# power_management.net
KiCad netlist of a schematic drawn in Altium Designer
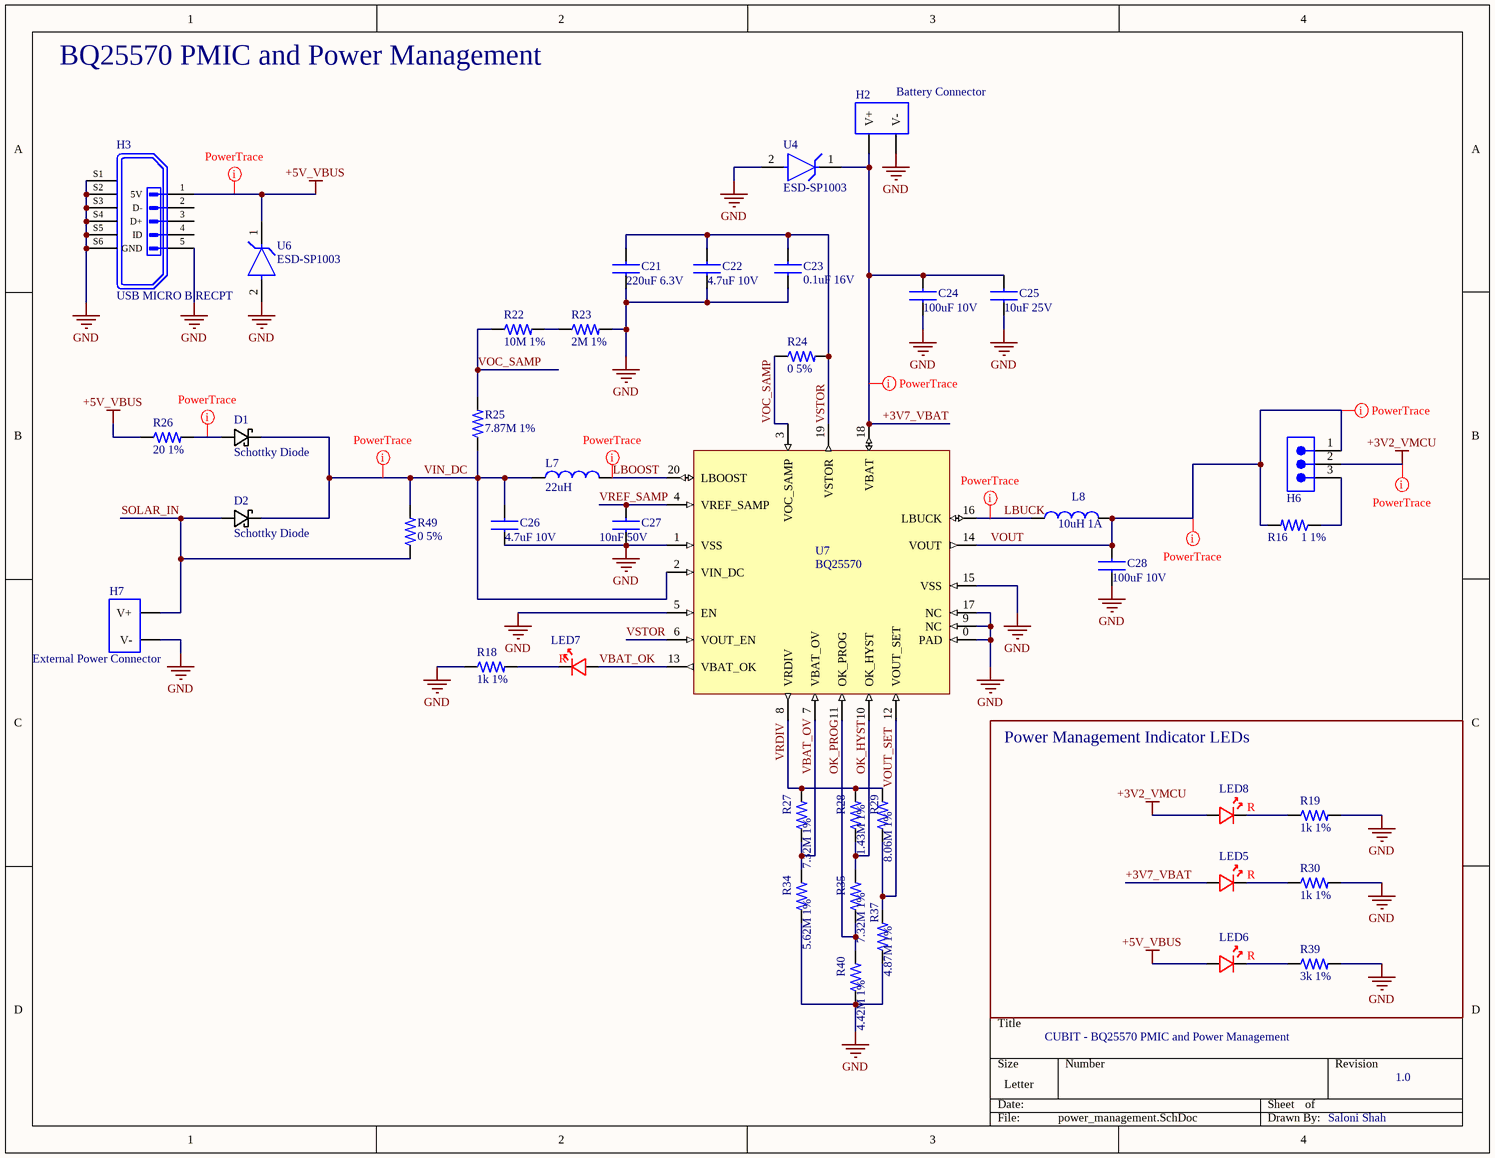
[diagram p0: power_management.SchDoc]

(export (version "E")
  (design (tool "Eeschema 10.0.6"))
  (components
    (comp (ref "C21")
      (value "220uF 6.3V")
      (footprint "Chip_1210_3.2x2.5")
      (description "Cap 220uF 6.3volts X5R 20%")
      (fields
        (field (name "MANUFACTURER") "Murata")
        (field (name "MANUFACTURER PART NUMBER") "GRM32ER60J227ME05L")
      )
      (libsource (lib "LPEDT_proj_lib") (part "GRM32ER60J227ME05L"))
    )
    (comp (ref "C22")
      (value "4.7uF 10V")
      (footprint "LPEDT_proj_lib:CAP_0603_1MM")
      (description "Cap CL10 Series 4.7 uF 10 V ±10 % Tolerance X5R SMT Multilayer Ceramic Capacitor")
      (fields
        (field (name "MANUFACTURER") "Samsung")
        (field (name "MANUFACTURER PART NUMBER") "CL10A475KP8NNNC")
      )
      (libsource (lib "LPEDT_proj_lib") (part "CL10A475KP8NNNC"))
    )
    (comp (ref "C23")
      (value "0.1uF 16V")
      (footprint "LPEDT_proj_lib:CAP_0603_1MM")
      (description "Cap Ceramic 0.1uF 16V X7R 10% SMD 0805 125°C Paper T/R")
      (fields
        (field (name "MANUFACTURER") "KEMET")
        (field (name "MANUFACTURER PART NUMBER") "C0805C104K4RACAUTO")
      )
      (libsource (lib "LPEDT_proj_lib") (part "C0805C104K4RACAUTO"))
    )
    (comp (ref "C24")
      (value "100uF 10V")
      (footprint "Chip_1210_3.2x2.5")
      (description "Cap 100uF ±20% 10V X5R 1210")
      (fields
        (field (name "MANUFACTURER") "Samsung")
        (field (name "MANUFACTURER PART NUMBER") "CL32A107MPVNNNE")
      )
      (libsource (lib "LPEDT_proj_lib") (part "CL32A107MPVNNNE"))
    )
    (comp (ref "C25")
      (value "10uF 25V")
      (footprint "LPEDT_proj_lib:CAP_0805_02X125")
      (description "Cap 0805 25 V 10 uF ±20% Tolerance X5R Monolithic Ceramic Chip Capacitor")
      (fields
        (field (name "MANUFACTURER") "Murata")
        (field (name "MANUFACTURER PART NUMBER") "GRM21BR61E106KA73K")
      )
      (libsource (lib "LPEDT_proj_lib") (part "GRM21BR61E106KA73K"))
    )
    (comp (ref "C26")
      (value "4.7uF 10V")
      (footprint "LPEDT_proj_lib:CAP_0603_1MM")
      (description "Cap CL10 Series 4.7 uF 10 V ±10 % Tolerance X5R SMT Multilayer Ceramic Capacitor")
      (fields
        (field (name "MANUFACTURER") "Samsung")
        (field (name "MANUFACTURER PART NUMBER") "CL10A475KP8NNNC")
      )
      (libsource (lib "LPEDT_proj_lib") (part "CL10A475KP8NNNC"))
    )
    (comp (ref "C27")
      (value "10nF 50V")
      (footprint "LPEDT_proj_lib:CAP_0805_02X125")
      (description "Cap 10nF ±10% 50V X7R 0805")
      (fields
        (field (name "MANUFACTURER") "Samsung")
        (field (name "MANUFACTURER PART NUMBER") "CL21B103KBCNNNC")
      )
      (libsource (lib "LPEDT_proj_lib") (part "CL21B103KBCNNNC"))
    )
    (comp (ref "C28")
      (value "100uF 10V")
      (footprint "Chip_1210_3.2x2.5")
      (description "Cap 100uF ±20% 10V X5R 1210")
      (fields
        (field (name "MANUFACTURER") "Samsung")
        (field (name "MANUFACTURER PART NUMBER") "CL32A107MPVNNNE")
      )
      (libsource (lib "LPEDT_proj_lib") (part "CL32A107MPVNNNE"))
    )
    (comp (ref "D1")
      (value "Schottky Diode")
      (footprint "SCHOTTKY4336X33N")
      (description "LSM115J Series 15 V 1 A Surface Mount Schottky Rectifier - DO-214BA")
      (fields
        (field (name "MANUFACTURER") "Microchip")
        (field (name "MANUFACTURER PART NUMBER") "LSM115JE3/TR13")
      )
      (libsource (lib "LPEDT_proj_lib") (part "LSM115JE3/TR13"))
    )
    (comp (ref "D2")
      (value "Schottky Diode")
      (footprint "SCHOTTKY4336X33N")
      (description "LSM115J Series 15 V 1 A Surface Mount Schottky Rectifier - DO-214BA")
      (fields
        (field (name "MANUFACTURER") "Microchip")
        (field (name "MANUFACTURER PART NUMBER") "LSM115JE3/TR13")
      )
      (libsource (lib "LPEDT_proj_lib") (part "LSM115JE3/TR13"))
    )
    (comp (ref "H2")
      (value "Battery Connector")
      (footprint "BAT_CONN")
      (description "2.00mm Pitch Mi ll System Wire-to-Board Header, Surface Mount, Single Row, Vertical, 2 Circuits")
      (fields (field (name "MANUFACTURER") "Molex") (field (name "MANUFACTURER PART NUMBER") "0554600272"))
      (libsource (lib "LPEDT_proj_lib") (part "0554600272"))
    )
    (comp (ref "H3")
      (value "USB MICRO B RECPT")
      (footprint "MICROUSB_AMPHENOL_10118194-0001LF")
      (description "USB - micro B USB 2.0 Receptacle Connector 5 Position Surface Mount, Right Angle; Through Hole")
      (fields
        (field (name "MANUFACTURER") "Amphenol FCI")
        (field (name "MANUFACTURER PART NUMBER") "10118194-0001LF")
      )
      (libsource (lib "LPEDT_proj_lib") (part "10118194-0001LF"))
    )
    (comp (ref "H6")
      (value "PREC003SAAN-RC")
      (footprint "LPEDT_proj_lib:3_PIN_100mil")
      (description "Connector Header Through Hole 3 position 0.100\" (2.54mm)")
      (fields (field (name "DIGIKEY PART") "S1012EC-03-ND") (field (name "LCSC PART#") "C429954"))
      (libsource (lib "LPEDT_proj_lib") (part "SW_3Pin_100mil_Switch"))
    )
    (comp (ref "H7")
      (value "External Power Connector")
      (footprint "LPEDT_proj_lib:2_PIN_100mil")
      (libsource (lib "LPEDT_proj_lib") (part "ext_pwr_conn"))
    )
    (comp (ref "L7")
      (value "22uH")
      (footprint "2_IND_3x3")
      (description "Inductor Power Shielded Wirewound 22uH 20% 1MHz Ferrite 0.87A 0.496Ohm DCR 1212 T/R")
      (fields
        (field (name "MANUFACTURER") "TDK")
        (field (name "MANUFACTURER PART NUMBER") "VLS3015CX-220M-1")
      )
      (libsource (lib "LPEDT_proj_lib") (part "VLS3015CX-220M-1"))
    )
    (comp (ref "L8")
      (value "10uH 1A")
      (footprint "2_chip_2.5x2")
      (description "Inductor Power Shielded Multi-Layer 10uH 20% 1MHz Metal 0.85A 0.46Ohm DCR 1008 T/R")
      (fields
        (field (name "MANUFACTURER") "Murata")
        (field (name "MANUFACTURER PART NUMBER") "1239AS-H-100M=P2")
      )
      (libsource (lib "LPEDT_proj_lib") (part "1239AS-H-100M=P2"))
    )
    (comp (ref "LED5")
      (value "150060RS75000")
      (footprint "LED_0603_RED_WL-SMCW")
      (description "LED Low-Power Uni-Color Red 630nm 2V 2-Pin Chip 0603(1608Metric) T/R")
      (fields (field (name "MANUFACTURER") "Wurth Electronics"))
      (libsource (lib "LPEDT_proj_lib") (part "150060RS75000"))
    )
    (comp (ref "LED6")
      (value "150060RS75000")
      (footprint "LED_0603_RED_WL-SMCW")
      (description "LED Low-Power Uni-Color Red 630nm 2V 2-Pin Chip 0603(1608Metric) T/R")
      (fields (field (name "MANUFACTURER") "Wurth Electronics"))
      (libsource (lib "LPEDT_proj_lib") (part "150060RS75000"))
    )
    (comp (ref "LED7")
      (value "150060RS75000")
      (footprint "LED_0603_RED_WL-SMCW")
      (description "LED Low-Power Uni-Color Red 630nm 2V 2-Pin Chip 0603(1608Metric) T/R")
      (fields (field (name "MANUFACTURER") "Wurth Electronics"))
      (libsource (lib "LPEDT_proj_lib") (part "150060RS75000"))
    )
    (comp (ref "LED8")
      (value "150060RS75000")
      (footprint "LED_0603_RED_WL-SMCW")
      (description "LED Low-Power Uni-Color Red 630nm 2V 2-Pin Chip 0603(1608Metric) T/R")
      (fields (field (name "MANUFACTURER") "Wurth Electronics"))
      (libsource (lib "LPEDT_proj_lib") (part "150060RS75000"))
    )
    (comp (ref "R16")
      (value "1 1%")
      (footprint "LPEDT_proj_lib:CAP_0603_1MM")
      (description "Res 1 Ohm 1% 1/10W ±200ppm/°C Molded SMD SMD Paper T/R")
      (fields
        (field (name "MANUFACTURER") "Yageo")
        (field (name "MANUFACTURER PART NUMBER") "RC0603FR-101RL")
      )
      (libsource (lib "LPEDT_proj_lib") (part "RC0603FR-101RL"))
    )
    (comp (ref "R18")
      (value "1k 1%")
      (footprint "2_Chip_0603_RMCF")
      (description "Res 1K Ohm 1% 0.1W(1/10W) ±100ppm/C Pad SMD Automotive T/R")
      (fields
        (field (name "MANUFACTURER") "Stackpole Electronics")
        (field (name "MANUFACTURER PART NUMBER") "RMCF0603FT1K00")
      )
      (libsource (lib "LPEDT_proj_lib") (part "RMCF0603FT1K00"))
    )
    (comp (ref "R19")
      (value "1k 1%")
      (footprint "2_Chip_0603_RMCF")
      (description "Res 1K Ohm 1% 0.1W(1/10W) ±100ppm/C Pad SMD Automotive T/R")
      (fields
        (field (name "MANUFACTURER") "Stackpole Electronics")
        (field (name "MANUFACTURER PART NUMBER") "RMCF0603FT1K00")
      )
      (libsource (lib "LPEDT_proj_lib") (part "RMCF0603FT1K00"))
    )
    (comp (ref "R22")
      (value "10M 1%")
      (footprint "2_Chip_0603_RMCF")
      (description "Res 10M Ohm 1% 1/10W ±200ppm/°C Molded SMD SMD Paper T/R")
      (fields
        (field (name "MANUFACTURER") "Stackpole Electronics")
        (field (name "MANUFACTURER PART NUMBER") "RMCF0603FT10M0")
      )
      (libsource (lib "LPEDT_proj_lib") (part "RMCF0603FT10M0"))
    )
    (comp (ref "R23")
      (value "2M 1%")
      (footprint "2_Chip_0603_RMCF")
      (description "RES 2M OHM 1% 1/10W 0603")
      (fields
        (field (name "MANUFACTURER") "Stackpole Electronics")
        (field (name "MANUFACTURER PART NUMBER") "RMCF0603FT2M00")
      )
      (libsource (lib "LPEDT_proj_lib") (part "RMCF0603FT2M00"))
    )
    (comp (ref "R24")
      (value "0 5%")
      (footprint "CAP_0402_1mm")
      (description "Res 0 Ohms ±5% 0.063 W 0402 Thick Film Surface Mount Chip Resistor")
      (fields
        (field (name "MANUFACTURER") "Samsung")
        (field (name "MANUFACTURER PART NUMBER") "RC1005J000CS")
      )
      (libsource (lib "LPEDT_proj_lib") (part "RC1005J000CS"))
    )
    (comp (ref "R25")
      (value "7.87M 1%")
      (footprint "2_Chip_0603_RMCF")
      (description "Res 7.87M Ohm 1% 1/10W ±200ppm/°C Molded SMD SMD Paper T/R")
      (fields
        (field (name "MANUFACTURER") "Stackpole Electronics")
        (field (name "MANUFACTURER PART NUMBER") "RMCF0603FT7M87")
      )
      (libsource (lib "LPEDT_proj_lib") (part "RMCF0603FT7M87"))
    )
    (comp (ref "R26")
      (value "20 1%")
      (footprint "2_Chip_0603_RMCF")
      (description "Res High Voltage 0603 20 Ohm 1/10W 1% SMD")
      (fields (field (name "MANUFACTURER") "Rohm") (field (name "MANUFACTURER PART NUMBER") "KTR03EZPF20R0"))
      (libsource (lib "LPEDT_proj_lib") (part "KTR03EZPF20R0"))
    )
    (comp (ref "R27")
      (value "7.32M 1%")
      (footprint "2_Chip_0603_RMCF")
      (description "Res 7.32M Ohm 1% 1/10W ±200ppm/°C Molded SMD SMD Paper T/R")
      (fields
        (field (name "MANUFACTURER") "Stackpole Electronics")
        (field (name "MANUFACTURER PART NUMBER") "RMCF0603FT7M32")
      )
      (libsource (lib "LPEDT_proj_lib") (part "RMCF0603FT7M32"))
    )
    (comp (ref "R28")
      (value "1.43M 1%")
      (footprint "2_Chip_0603_RMCF")
      (description "Res 1.43M Ohm 1% 1/10W ±200ppm/°C Molded SMD SMD Paper T/R")
      (fields
        (field (name "MANUFACTURER") "Stackpole Electronics")
        (field (name "MANUFACTURER PART NUMBER") "RMCF0603FT1M43")
      )
      (libsource (lib "LPEDT_proj_lib") (part "RMCF0603FT1M43"))
    )
    (comp (ref "R29")
      (value "8.06M 1%")
      (footprint "2_Chip_0603_RMCF")
      (description "Res 8.06M Ohm 1% 1/10W ±200ppm/°C Molded SMD SMD Paper T/R")
      (fields
        (field (name "MANUFACTURER") "Stackpole Electronics")
        (field (name "MANUFACTURER PART NUMBER") "RMCF0603FT8M06")
      )
      (libsource (lib "LPEDT_proj_lib") (part "RMCF0603FT8M06"))
    )
    (comp (ref "R30")
      (value "1k 1%")
      (footprint "2_Chip_0603_RMCF")
      (description "Res 1K Ohm 1% 0.1W(1/10W) ±100ppm/C Pad SMD Automotive T/R")
      (fields
        (field (name "MANUFACTURER") "Stackpole Electronics")
        (field (name "MANUFACTURER PART NUMBER") "RMCF0603FT1K00")
      )
      (libsource (lib "LPEDT_proj_lib") (part "RMCF0603FT1K00"))
    )
    (comp (ref "R34")
      (value "5.62M 1%")
      (footprint "2_Chip_0603_RMCF")
      (description "Res 5.62M Ohm 1% 1/10W ±200ppm/°C Molded SMD SMD Paper T/R")
      (fields
        (field (name "MANUFACTURER") "Stackpole Electronics")
        (field (name "MANUFACTURER PART NUMBER") "RMCF0603FT5M62")
      )
      (libsource (lib "LPEDT_proj_lib") (part "RMCF0603FT5M62"))
    )
    (comp (ref "R35")
      (value "7.32M 1%")
      (footprint "2_Chip_0603_RMCF")
      (description "Res 7.32M Ohm 1% 1/10W ±200ppm/°C Molded SMD SMD Paper T/R")
      (fields
        (field (name "MANUFACTURER") "Stackpole Electronics")
        (field (name "MANUFACTURER PART NUMBER") "RMCF0603FT7M32")
      )
      (libsource (lib "LPEDT_proj_lib") (part "RMCF0603FT7M32"))
    )
    (comp (ref "R37")
      (value "4.87M 1%")
      (footprint "2_Chip_0603_RMCF")
      (description "Res 4.87M Ohm 1% 1/10W ±200ppm/°C Molded SMD SMD Paper T/R")
      (fields
        (field (name "MANUFACTURER") "Stackpole Electronics")
        (field (name "MANUFACTURER PART NUMBER") "RMCF0603FT4M87")
      )
      (libsource (lib "LPEDT_proj_lib") (part "RMCF0603FT4M87"))
    )
    (comp (ref "R39")
      (value "3k 1%")
      (footprint "LPEDT_proj_lib:CAP_0603_1MM")
      (description "Res 3000Ω ± 1.00% 0.1W ± 100ppm/℃ 0603")
      (fields
        (field (name "MANUFACTURER") "Yageo")
        (field (name "MANUFACTURER PART NUMBER") "RC0603FR-073KL")
      )
      (libsource (lib "LPEDT_proj_lib") (part "RC0603FR-073KL"))
    )
    (comp (ref "R40")
      (value "4.42M 1%")
      (footprint "2_Chip_0603_RMCF")
      (description "Res 4.42M Ohm 1% 1/10W ±200ppm/°C Molded SMD SMD Paper T/R")
      (fields
        (field (name "MANUFACTURER") "Stackpole Electronics")
        (field (name "MANUFACTURER PART NUMBER") "RMCF0603FT4M42")
      )
      (libsource (lib "LPEDT_proj_lib") (part "RMCF0603FT4M42"))
    )
    (comp (ref "R49")
      (value "0 5%")
      (footprint "CAP_0402_1mm")
      (description "Res 0 Ohms ±5% 0.063 W 0402 Thick Film Surface Mount Chip Resistor")
      (fields
        (field (name "MANUFACTURER") "Samsung")
        (field (name "MANUFACTURER PART NUMBER") "RC1005J000CS")
      )
      (libsource (lib "LPEDT_proj_lib") (part "RC1005J000CS"))
    )
    (comp (ref "U4")
      (value "ESD-SP1003")
      (footprint "Littelfuse_Inc_SP1003_MFG")
      (description "TVS DIODE 5VWM 12VC SOD723")
      (fields
        (field (name "MANUFACTURER") "Littelfuse")
        (field (name "MANUFACTURER PART NUMBER") "SP1003-01DTG")
      )
      (libsource (lib "LPEDT_proj_lib") (part "SP1003-01DTG"))
    )
    (comp (ref "U6")
      (value "ESD-SP1003")
      (footprint "Littelfuse_Inc_SP1003_MFG")
      (description "TVS DIODE 5VWM 12VC SOD723")
      (fields
        (field (name "MANUFACTURER") "Littelfuse")
        (field (name "MANUFACTURER PART NUMBER") "SP1003-01DTG")
      )
      (libsource (lib "LPEDT_proj_lib") (part "SP1003-01DTG"))
    )
    (comp (ref "U7")
      (value "BQ25570")
      (footprint "21_QFN_35x35")
      (description "Switching Battery Charger Li-Ion/Li-Pol/Supercapacitor 110mA 2.2V to 5.5V 20-Pin VQFN EP T/R")
      (fields
        (field (name "MANUFACTURER") "Texas Instruments")
        (field (name "MANUFACTURER PART NUMBER") "BQ25570RGRT")
      )
      (libsource (lib "LPEDT_proj_lib") (part "BQ25570RGRT"))
    )
  )
  (nets
    (net (code "1") (name "+3V2_VMCU") (class "Default")
      (node (ref "H6") (pin "2") (pinfunction "2_2") (pintype "passive"))
      (node (ref "LED8") (pin "A") (pinfunction "A_A") (pintype "passive"))
    )
    (net (code "2") (name "+5V_VBUS") (class "Default")
      (node (ref "H3") (pin "1") (pinfunction "5V_1") (pintype "power_in"))
      (node (ref "LED6") (pin "A") (pinfunction "A_A") (pintype "passive"))
      (node (ref "R26") (pin "1") (pinfunction "1_1") (pintype "passive"))
      (node (ref "U6") (pin "1") (pinfunction "C_1") (pintype "passive"))
    )
    (net (code "3") (name "/+3V7_VBAT") (class "Default")
      (node (ref "C24") (pin "1") (pinfunction "1_1") (pintype "passive"))
      (node (ref "C25") (pin "1") (pinfunction "1_1") (pintype "passive"))
      (node (ref "H2") (pin "V+") (pinfunction "V+_V+") (pintype "passive"))
      (node (ref "LED5") (pin "A") (pinfunction "A_A") (pintype "passive"))
      (node (ref "U4") (pin "1") (pinfunction "C_1") (pintype "passive"))
      (node (ref "U7") (pin "18") (pinfunction "VBAT_18") (pintype "bidirectional"))
    )
    (net (code "4") (name "/LBOOST") (class "Default")
      (node (ref "L7") (pin "2") (pinfunction "2_2") (pintype "passive"))
      (node (ref "U7") (pin "20") (pinfunction "LBOOST_20") (pintype "bidirectional"))
    )
    (net (code "5") (name "/LBUCK") (class "Default")
      (node (ref "L8") (pin "1") (pinfunction "1_1") (pintype "passive"))
      (node (ref "U7") (pin "16") (pinfunction "LBUCK_16") (pintype "bidirectional"))
    )
    (net (code "6") (name "/OK_HYST") (class "Default")
      (node (ref "R28") (pin "1") (pinfunction "1_1") (pintype "passive"))
      (node (ref "R35") (pin "2") (pinfunction "2_2") (pintype "passive"))
      (node (ref "U7") (pin "10") (pinfunction "OK_HYST_10") (pintype "input"))
    )
    (net (code "7") (name "/OK_PROG") (class "Default")
      (node (ref "R35") (pin "1") (pinfunction "1_1") (pintype "passive"))
      (node (ref "R40") (pin "2") (pinfunction "2_2") (pintype "passive"))
      (node (ref "U7") (pin "11") (pinfunction "OK_PROG_11") (pintype "input"))
    )
    (net (code "8") (name "/SOLAR_IN") (class "Default")
      (node (ref "D2") (pin "A") (pinfunction "A_A") (pintype "passive"))
      (node (ref "H7") (pin "1") (pinfunction "V+_1") (pintype "passive"))
      (node (ref "R49") (pin "1") (pinfunction "1_1") (pintype "passive"))
    )
    (net (code "9") (name "/VBAT_OK") (class "Default")
      (node (ref "LED7") (pin "A") (pinfunction "A_A") (pintype "passive"))
      (node (ref "U7") (pin "13") (pinfunction "VBAT_OK_13") (pintype "output"))
    )
    (net (code "10") (name "/VBAT_OV") (class "Default")
      (node (ref "R27") (pin "1") (pinfunction "1_1") (pintype "passive"))
      (node (ref "R34") (pin "2") (pinfunction "2_2") (pintype "passive"))
      (node (ref "U7") (pin "7") (pinfunction "VBAT_OV_7") (pintype "input"))
    )
    (net (code "11") (name "/VIN_DC") (class "Default")
      (node (ref "C26") (pin "1") (pinfunction "1_1") (pintype "passive"))
      (node (ref "D1") (pin "C") (pinfunction "C_C") (pintype "passive"))
      (node (ref "D2") (pin "C") (pinfunction "C_C") (pintype "passive"))
      (node (ref "L7") (pin "1") (pinfunction "1_1") (pintype "passive"))
      (node (ref "R25") (pin "1") (pinfunction "1_1") (pintype "passive"))
      (node (ref "R49") (pin "2") (pinfunction "2_2") (pintype "passive"))
      (node (ref "U7") (pin "2") (pinfunction "VIN_DC_2") (pintype "input"))
    )
    (net (code "12") (name "/VOC_SAMP") (class "Default")
      (node (ref "R22") (pin "1") (pinfunction "1_1") (pintype "passive"))
      (node (ref "R24") (pin "1") (pinfunction "1_1") (pintype "passive"))
      (node (ref "R25") (pin "2") (pinfunction "2_2") (pintype "passive"))
      (node (ref "U7") (pin "3") (pinfunction "VOC_SAMP_3") (pintype "input"))
    )
    (net (code "13") (name "/VOUT") (class "Default")
      (node (ref "C28") (pin "1") (pinfunction "1_1") (pintype "passive"))
      (node (ref "H6") (pin "1") (pinfunction "1_1") (pintype "passive"))
      (node (ref "L8") (pin "2") (pinfunction "2_2") (pintype "passive"))
      (node (ref "R16") (pin "2") (pinfunction "2_2") (pintype "passive"))
      (node (ref "U7") (pin "14") (pinfunction "VOUT_14") (pintype "output"))
    )
    (net (code "14") (name "/VOUT_SET") (class "Default")
      (node (ref "R29") (pin "1") (pinfunction "1_1") (pintype "passive"))
      (node (ref "R37") (pin "2") (pinfunction "2_2") (pintype "passive"))
      (node (ref "U7") (pin "12") (pinfunction "VOUT_SET_12") (pintype "input"))
    )
    (net (code "15") (name "/VRDIV") (class "Default")
      (node (ref "R27") (pin "2") (pinfunction "2_2") (pintype "passive"))
      (node (ref "R28") (pin "2") (pinfunction "2_2") (pintype "passive"))
      (node (ref "R29") (pin "2") (pinfunction "2_2") (pintype "passive"))
      (node (ref "U7") (pin "8") (pinfunction "VRDIV_8") (pintype "output"))
    )
    (net (code "16") (name "/VREF_SAMP") (class "Default")
      (node (ref "C27") (pin "1") (pinfunction "1_1") (pintype "passive"))
      (node (ref "U7") (pin "4") (pinfunction "VREF_SAMP_4") (pintype "input"))
    )
    (net (code "17") (name "/VSTOR") (class "Default")
      (node (ref "C21") (pin "1") (pinfunction "1_1") (pintype "passive"))
      (node (ref "C22") (pin "1") (pinfunction "1_1") (pintype "passive"))
      (node (ref "C23") (pin "1") (pinfunction "1_1") (pintype "passive"))
      (node (ref "R24") (pin "2") (pinfunction "2_2") (pintype "passive"))
      (node (ref "U7") (pin "19") (pinfunction "VSTOR_19") (pintype "output"))
      (node (ref "U7") (pin "6") (pinfunction "VOUT_EN_6") (pintype "input"))
    )
    (net (code "18") (name "GND") (class "Default")
      (node (ref "C21") (pin "2") (pinfunction "2_2") (pintype "passive"))
      (node (ref "C22") (pin "2") (pinfunction "2_2") (pintype "passive"))
      (node (ref "C23") (pin "2") (pinfunction "2_2") (pintype "passive"))
      (node (ref "C24") (pin "2") (pinfunction "2_2") (pintype "passive"))
      (node (ref "C25") (pin "2") (pinfunction "2_2") (pintype "passive"))
      (node (ref "C26") (pin "2") (pinfunction "2_2") (pintype "passive"))
      (node (ref "C27") (pin "2") (pinfunction "2_2") (pintype "passive"))
      (node (ref "C28") (pin "2") (pinfunction "2_2") (pintype "passive"))
      (node (ref "H2") (pin "V-") (pinfunction "V-_V-") (pintype "passive"))
      (node (ref "H3") (pin "5") (pinfunction "GND_5") (pintype "passive"))
      (node (ref "H3") (pin "S1") (pinfunction "S1_S1") (pintype "passive"))
      (node (ref "H3") (pin "S2") (pinfunction "S2_S2") (pintype "passive"))
      (node (ref "H3") (pin "S3") (pinfunction "S3_S3") (pintype "passive"))
      (node (ref "H3") (pin "S4") (pinfunction "S4_S4") (pintype "passive"))
      (node (ref "H3") (pin "S5") (pinfunction "S5_S5") (pintype "passive"))
      (node (ref "H3") (pin "S6") (pinfunction "S6_S6") (pintype "passive"))
      (node (ref "H7") (pin "2") (pinfunction "V-_2") (pintype "passive"))
      (node (ref "R18") (pin "1") (pinfunction "1_1") (pintype "passive"))
      (node (ref "R19") (pin "2") (pinfunction "2_2") (pintype "passive"))
      (node (ref "R23") (pin "2") (pinfunction "2_2") (pintype "passive"))
      (node (ref "R30") (pin "2") (pinfunction "2_2") (pintype "passive"))
      (node (ref "R34") (pin "1") (pinfunction "1_1") (pintype "passive"))
      (node (ref "R37") (pin "1") (pinfunction "1_1") (pintype "passive"))
      (node (ref "R39") (pin "2") (pinfunction "2_2") (pintype "passive"))
      (node (ref "R40") (pin "1") (pinfunction "1_1") (pintype "passive"))
      (node (ref "U4") (pin "2") (pinfunction "A_2") (pintype "passive"))
      (node (ref "U6") (pin "2") (pinfunction "A_2") (pintype "passive"))
      (node (ref "U7") (pin "0") (pinfunction "PAD_0") (pintype "input"))
      (node (ref "U7") (pin "1") (pinfunction "VSS_1") (pintype "input"))
      (node (ref "U7") (pin "15") (pinfunction "VSS_15") (pintype "input"))
      (node (ref "U7") (pin "17") (pinfunction "NC_17") (pintype "input"))
      (node (ref "U7") (pin "5") (pinfunction "EN_5") (pintype "input"))
      (node (ref "U7") (pin "9") (pinfunction "NC_9") (pintype "input"))
    )
    (net (code "19") (name "Net-(D1-PadA)") (class "Default")
      (node (ref "D1") (pin "A") (pinfunction "A_A") (pintype "passive"))
      (node (ref "R26") (pin "2") (pinfunction "2_2") (pintype "passive"))
    )
    (net (code "20") (name "Net-(H6-Pad3)") (class "Default")
      (node (ref "H6") (pin "3") (pinfunction "3_3") (pintype "passive"))
      (node (ref "R16") (pin "1") (pinfunction "1_1") (pintype "passive"))
    )
    (net (code "21") (name "Net-(LED5-PadC)") (class "Default")
      (node (ref "LED5") (pin "C") (pinfunction "C_C") (pintype "passive"))
      (node (ref "R30") (pin "1") (pinfunction "1_1") (pintype "passive"))
    )
    (net (code "22") (name "Net-(LED6-PadC)") (class "Default")
      (node (ref "LED6") (pin "C") (pinfunction "C_C") (pintype "passive"))
      (node (ref "R39") (pin "1") (pinfunction "1_1") (pintype "passive"))
    )
    (net (code "23") (name "Net-(LED7-PadC)") (class "Default")
      (node (ref "LED7") (pin "C") (pinfunction "C_C") (pintype "passive"))
      (node (ref "R18") (pin "2") (pinfunction "2_2") (pintype "passive"))
    )
    (net (code "24") (name "Net-(LED8-PadC)") (class "Default")
      (node (ref "LED8") (pin "C") (pinfunction "C_C") (pintype "passive"))
      (node (ref "R19") (pin "1") (pinfunction "1_1") (pintype "passive"))
    )
    (net (code "25") (name "Net-(R22-Pad2)") (class "Default")
      (node (ref "R22") (pin "2") (pinfunction "2_2") (pintype "passive"))
      (node (ref "R23") (pin "1") (pinfunction "1_1") (pintype "passive"))
    )
    (net (code "26") (name "unconnected-(H3-D+-Pad3)") (class "Default")
      (node (ref "H3") (pin "3") (pinfunction "D+_3") (pintype "passive"))
    )
    (net (code "27") (name "unconnected-(H3-D--Pad2)") (class "Default")
      (node (ref "H3") (pin "2") (pinfunction "D-_2") (pintype "passive"))
    )
    (net (code "28") (name "unconnected-(H3-ID-Pad4)") (class "Default")
      (node (ref "H3") (pin "4") (pinfunction "ID_4") (pintype "passive"))
    )
  )
)
